# Drive.net
KiCad netlist of a schematic drawn in Altium Designer
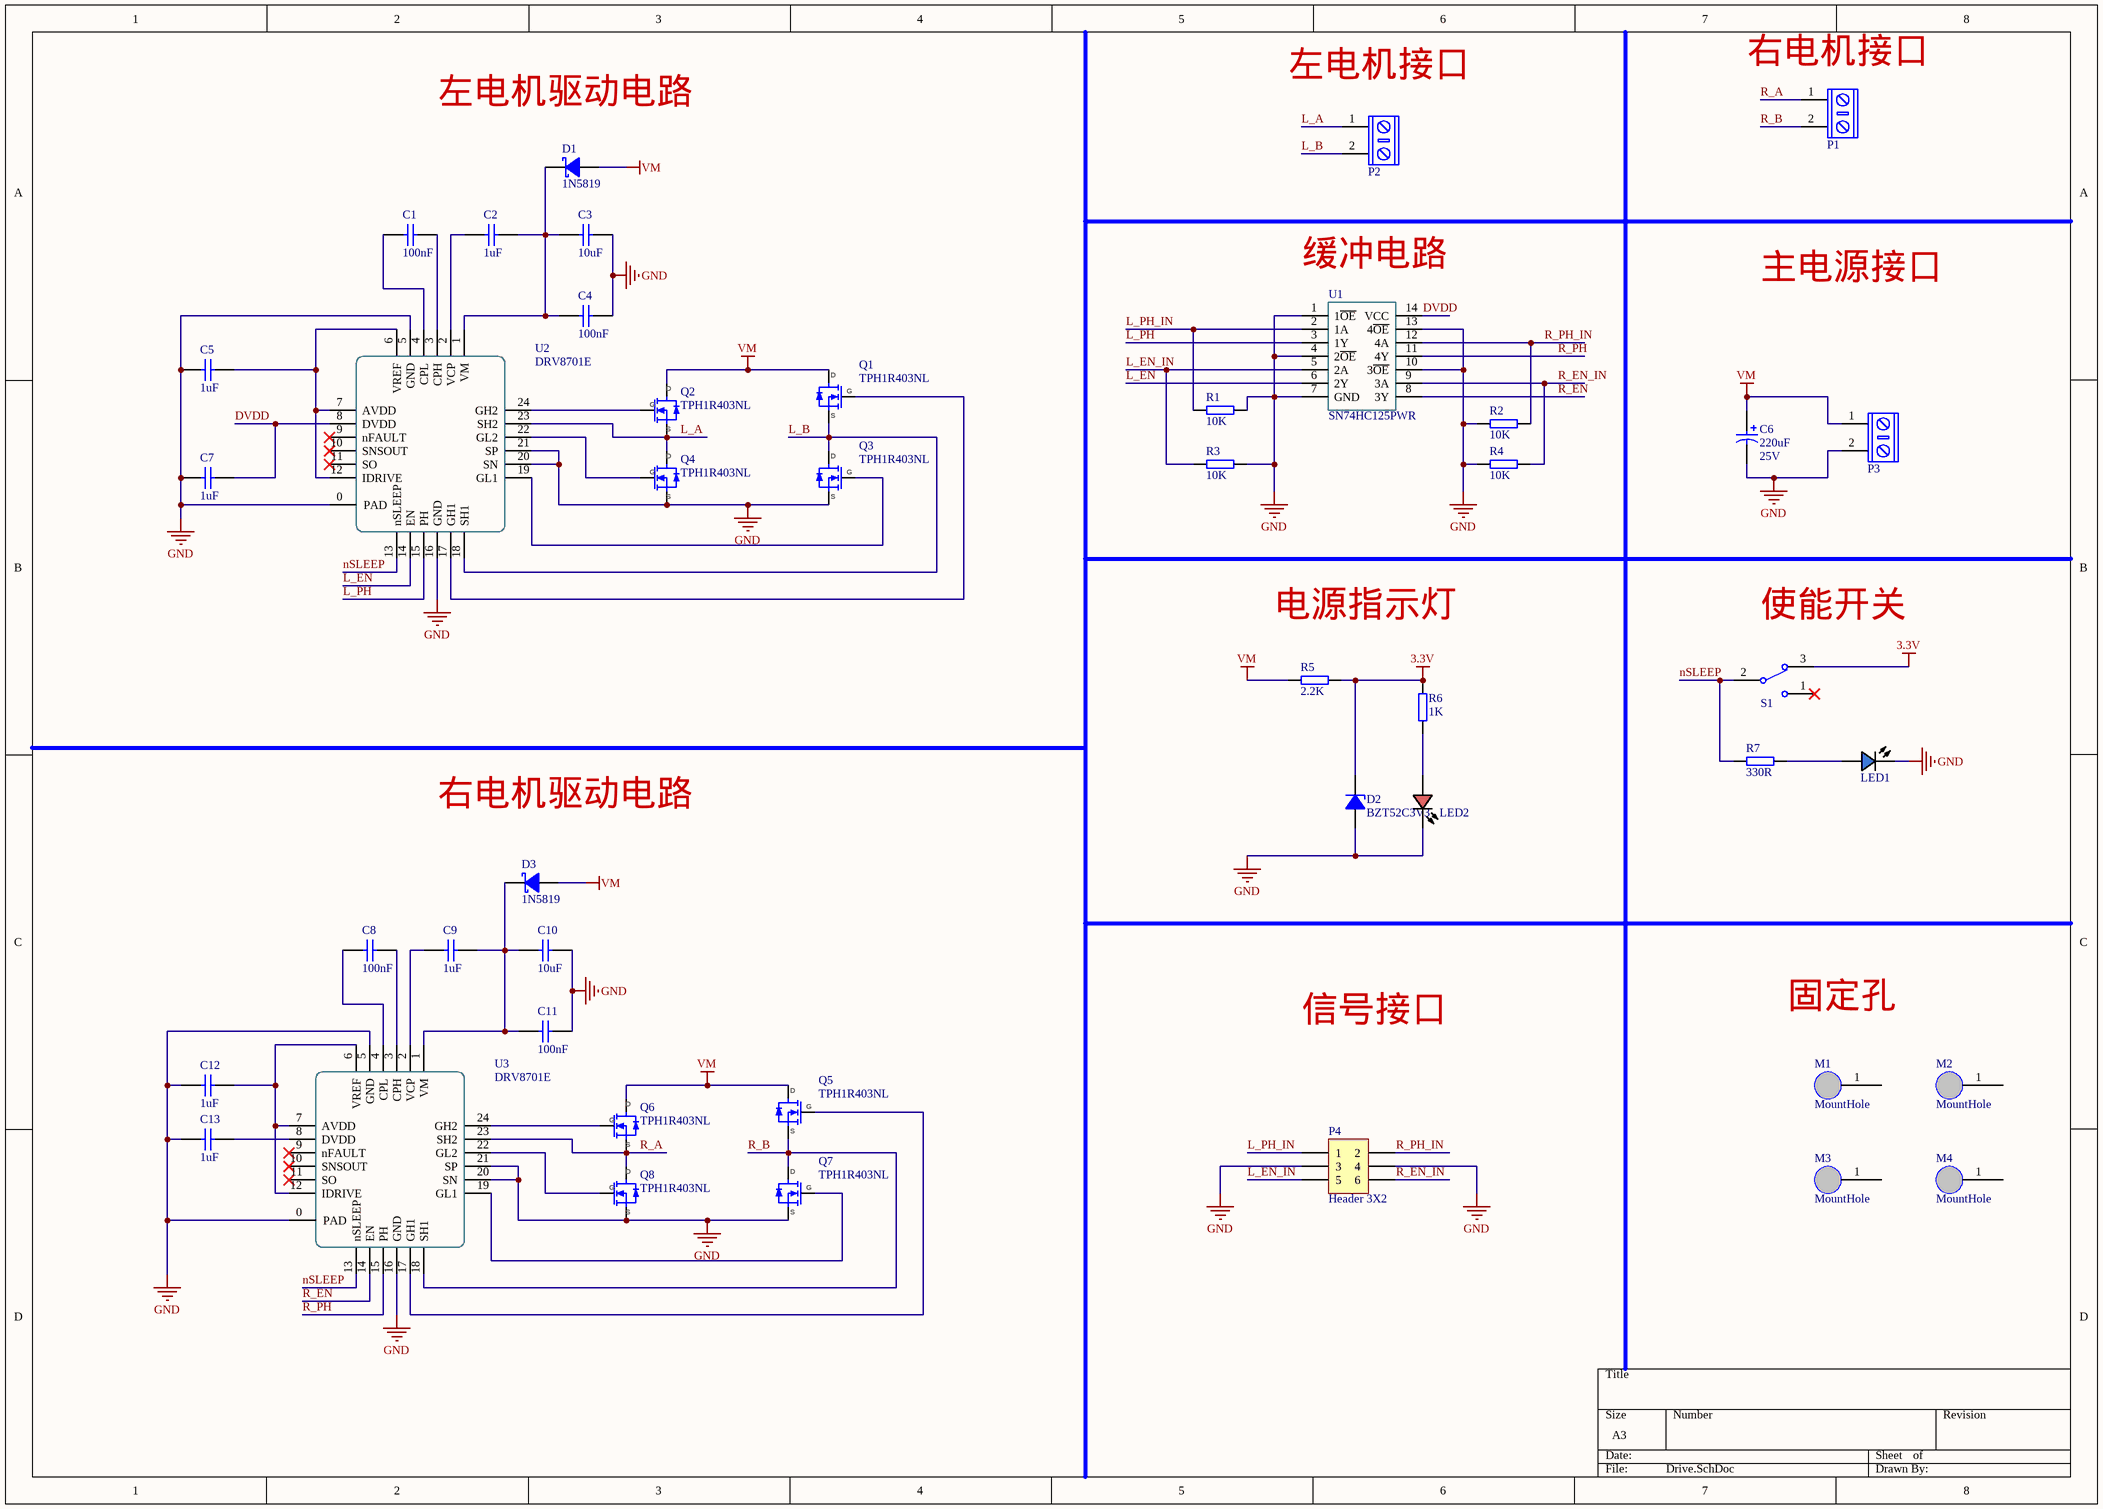
[diagram p0: Drive.SchDoc]

(export (version "E")
  (design (tool "Eeschema 10.0.6"))
  (components
    (comp (ref "C1")
      (value "100nF")
      (footprint "CAPC1608[0603]S-N")
      (description "贴片电容")
      (fields
        (field (name "VOLTAGE") "50V")
        (field (name "TOLERANCE") "±10%")
        (field (name "PUBLISHER") "Altium Limited")
      )
      (libsource (lib "DRV8701_DualMotorDriver") (part "Cap-Chip_1"))
    )
    (comp (ref "C2")
      (value "1uF")
      (footprint "CAPC1608[0603]S-N")
      (description "贴片电容")
      (fields
        (field (name "VOLTAGE") "25V")
        (field (name "TOLERANCE") "±10%")
        (field (name "PUBLISHER") "Altium Limited")
      )
      (libsource (lib "DRV8701_DualMotorDriver") (part "Cap-Chip_2"))
    )
    (comp (ref "C3")
      (value "10uF")
      (footprint "CAPC1608[0603]S-N")
      (description "贴片电容")
      (fields
        (field (name "VOLTAGE") "25V")
        (field (name "TOLERANCE") "±10%")
        (field (name "PUBLISHER") "Altium Limited")
      )
      (libsource (lib "DRV8701_DualMotorDriver") (part "Cap-Chip"))
    )
    (comp (ref "C4")
      (value "100nF")
      (footprint "CAPC1608[0603]S-N")
      (description "贴片电容")
      (fields
        (field (name "VOLTAGE") "50V")
        (field (name "TOLERANCE") "±10%")
        (field (name "PUBLISHER") "Altium Limited")
      )
      (libsource (lib "DRV8701_DualMotorDriver") (part "Cap-Chip_1"))
    )
    (comp (ref "C5")
      (value "1uF")
      (footprint "CAPC1608[0603]S-N")
      (description "贴片电容")
      (fields
        (field (name "VOLTAGE") "25V")
        (field (name "TOLERANCE") "±10%")
        (field (name "PUBLISHER") "Altium Limited")
      )
      (libsource (lib "DRV8701_DualMotorDriver") (part "Cap-Chip_2"))
    )
    (comp (ref "C6")
      (value "220uF")
      (footprint "CAPS6.3")
      (description "Polarized Capacitor (Radial)")
      (fields
        (field (name "VOLTAGE") "25V")
        (field (name "Comment") "220uF 25V")
        (field (name "PUBLISHER") "Altium Limited")
      )
      (libsource (lib "DRV8701_DualMotorDriver") (part "Cap-Elect"))
    )
    (comp (ref "C7")
      (value "1uF")
      (footprint "CAPC1608[0603]S-N")
      (description "贴片电容")
      (fields
        (field (name "VOLTAGE") "25V")
        (field (name "TOLERANCE") "±10%")
        (field (name "PUBLISHER") "Altium Limited")
      )
      (libsource (lib "DRV8701_DualMotorDriver") (part "Cap-Chip_2"))
    )
    (comp (ref "C8")
      (value "100nF")
      (footprint "CAPC1608[0603]S-N")
      (description "贴片电容")
      (fields
        (field (name "VOLTAGE") "50V")
        (field (name "TOLERANCE") "±10%")
        (field (name "PUBLISHER") "Altium Limited")
      )
      (libsource (lib "DRV8701_DualMotorDriver") (part "Cap-Chip_1"))
    )
    (comp (ref "C9")
      (value "1uF")
      (footprint "CAPC1608[0603]S-N")
      (description "贴片电容")
      (fields
        (field (name "VOLTAGE") "25V")
        (field (name "TOLERANCE") "±10%")
        (field (name "PUBLISHER") "Altium Limited")
      )
      (libsource (lib "DRV8701_DualMotorDriver") (part "Cap-Chip_2"))
    )
    (comp (ref "C10")
      (value "10uF")
      (footprint "CAPC1608[0603]S-N")
      (description "贴片电容")
      (fields
        (field (name "VOLTAGE") "25V")
        (field (name "TOLERANCE") "±10%")
        (field (name "PUBLISHER") "Altium Limited")
      )
      (libsource (lib "DRV8701_DualMotorDriver") (part "Cap-Chip"))
    )
    (comp (ref "C11")
      (value "100nF")
      (footprint "CAPC1608[0603]S-N")
      (description "贴片电容")
      (fields
        (field (name "VOLTAGE") "50V")
        (field (name "TOLERANCE") "±10%")
        (field (name "PUBLISHER") "Altium Limited")
      )
      (libsource (lib "DRV8701_DualMotorDriver") (part "Cap-Chip_1"))
    )
    (comp (ref "C12")
      (value "1uF")
      (footprint "CAPC1608[0603]S-N")
      (description "贴片电容")
      (fields
        (field (name "VOLTAGE") "25V")
        (field (name "TOLERANCE") "±10%")
        (field (name "PUBLISHER") "Altium Limited")
      )
      (libsource (lib "DRV8701_DualMotorDriver") (part "Cap-Chip_2"))
    )
    (comp (ref "C13")
      (value "1uF")
      (footprint "CAPC1608[0603]S-N")
      (description "贴片电容")
      (fields
        (field (name "VOLTAGE") "25V")
        (field (name "TOLERANCE") "±10%")
        (field (name "PUBLISHER") "Altium Limited")
      )
      (libsource (lib "DRV8701_DualMotorDriver") (part "Cap-Chip_2"))
    )
    (comp (ref "D1")
      (value "1N5819")
      (footprint "SOD-123-L")
      (description "肖特基二极管 Diode")
      (fields (field (name "PARTNUMBER") "1N5819") (field (name "PUBLISHER") "Altium Limited"))
      (libsource (lib "DRV8701_DualMotorDriver") (part "Diode Schottky"))
    )
    (comp (ref "D2")
      (value "BZT52C3V3")
      (footprint "SOD-123-L")
      (description "3.3V稳压二极管 SOD-123")
      (fields (field (name "PUBLISHER") "Altium Limited"))
      (libsource (lib "DRV8701_DualMotorDriver") (part "Diode Zen"))
    )
    (comp (ref "D3")
      (value "1N5819")
      (footprint "SOD-123-L")
      (description "肖特基二极管 Diode")
      (fields (field (name "PARTNUMBER") "1N5819") (field (name "PUBLISHER") "Altium Limited"))
      (libsource (lib "DRV8701_DualMotorDriver") (part "Diode Schottky"))
    )
    (comp (ref "LED1")
      (value "Blue")
      (footprint "LEDC1608(0603)")
      (description "Typical Chip LED")
      (fields (field (name "PUBLISHER") "Altium Limited"))
      (libsource (lib "DRV8701_DualMotorDriver") (part "LED Chip Blue"))
    )
    (comp (ref "LED2")
      (value "~")
      (footprint "LEDC1608(0603)")
      (description "Typical Chip LED")
      (fields (field (name "PUBLISHER") "Altium Limited"))
      (libsource (lib "DRV8701_DualMotorDriver") (part "LED Chip Red"))
    )
    (comp (ref "M1")
      (value "MountHole")
      (footprint "M3-MountSlot")
      (description "固定孔")
      (libsource (lib "DRV8701_DualMotorDriver") (part "MountHole"))
    )
    (comp (ref "M2")
      (value "MountHole")
      (footprint "M3-MountSlot")
      (description "固定孔")
      (libsource (lib "DRV8701_DualMotorDriver") (part "MountHole"))
    )
    (comp (ref "M3")
      (value "MountHole")
      (footprint "M3-MountSlot")
      (description "固定孔")
      (libsource (lib "DRV8701_DualMotorDriver") (part "MountHole"))
    )
    (comp (ref "M4")
      (value "MountHole")
      (footprint "M3-MountSlot")
      (description "固定孔")
      (libsource (lib "DRV8701_DualMotorDriver") (part "MountHole"))
    )
    (comp (ref "P1")
      (value "KF/WJ/DG 30x connecter")
      (footprint "KF/WJ/DG 301-2p-5.0mm")
      (description "接线端子 2Pin")
      (libsource (lib "DRV8701_DualMotorDriver") (part "KF/WJ/DG 30x"))
    )
    (comp (ref "P2")
      (value "KF/WJ/DG 30x connecter")
      (footprint "KF/WJ/DG 301-2p-5.0mm")
      (description "接线端子 2Pin")
      (libsource (lib "DRV8701_DualMotorDriver") (part "KF/WJ/DG 30x"))
    )
    (comp (ref "P3")
      (value "KF/WJ/DG 30x connecter")
      (footprint "KF/WJ/DG 301-2p-5.0mm")
      (description "接线端子 2Pin")
      (libsource (lib "DRV8701_DualMotorDriver") (part "KF/WJ/DG 30x"))
    )
    (comp (ref "P4")
      (value "Header 3X2")
      (footprint "HDR2X3")
      (description "Header, 3-Pin, Dual row")
      (fields (field (name "PUBLISHER") "Altium Limited"))
      (libsource (lib "DRV8701_DualMotorDriver") (part "Header 3X2"))
    )
    (comp (ref "Q1")
      (value "TPH1R403NL")
      (footprint "DFN5x6")
      (description "东芝 N沟 MOS")
      (libsource (lib "DRV8701_DualMotorDriver") (part "TPH1R403NL"))
    )
    (comp (ref "Q2")
      (value "TPH1R403NL")
      (footprint "DFN5x6")
      (description "东芝 N沟 MOS")
      (libsource (lib "DRV8701_DualMotorDriver") (part "TPH1R403NL"))
    )
    (comp (ref "Q3")
      (value "TPH1R403NL")
      (footprint "DFN5x6")
      (description "东芝 N沟 MOS")
      (libsource (lib "DRV8701_DualMotorDriver") (part "TPH1R403NL"))
    )
    (comp (ref "Q4")
      (value "TPH1R403NL")
      (footprint "DFN5x6")
      (description "东芝 N沟 MOS")
      (libsource (lib "DRV8701_DualMotorDriver") (part "TPH1R403NL"))
    )
    (comp (ref "Q5")
      (value "TPH1R403NL")
      (footprint "DFN5x6")
      (description "东芝 N沟 MOS")
      (libsource (lib "DRV8701_DualMotorDriver") (part "TPH1R403NL"))
    )
    (comp (ref "Q6")
      (value "TPH1R403NL")
      (footprint "DFN5x6")
      (description "东芝 N沟 MOS")
      (libsource (lib "DRV8701_DualMotorDriver") (part "TPH1R403NL"))
    )
    (comp (ref "Q7")
      (value "TPH1R403NL")
      (footprint "DFN5x6")
      (description "东芝 N沟 MOS")
      (libsource (lib "DRV8701_DualMotorDriver") (part "TPH1R403NL"))
    )
    (comp (ref "Q8")
      (value "TPH1R403NL")
      (footprint "DFN5x6")
      (description "东芝 N沟 MOS")
      (libsource (lib "DRV8701_DualMotorDriver") (part "TPH1R403NL"))
    )
    (comp (ref "R1")
      (value "10K")
      (footprint "RESC1608[0603]S-N")
      (description "贴片电阻")
      (fields
        (field (name "TOLERANCE") "±1%")
        (field (name "Comment") "10K ±1%")
        (field (name "PUBLISHER") "Altium Limited")
      )
      (libsource (lib "DRV8701_DualMotorDriver") (part "Res-Chip_1"))
    )
    (comp (ref "R2")
      (value "10K")
      (footprint "RESC1608[0603]S-N")
      (description "贴片电阻")
      (fields
        (field (name "TOLERANCE") "±1%")
        (field (name "Comment") "10K ±1%")
        (field (name "PUBLISHER") "Altium Limited")
      )
      (libsource (lib "DRV8701_DualMotorDriver") (part "Res-Chip_1"))
    )
    (comp (ref "R3")
      (value "10K")
      (footprint "RESC1608[0603]S-N")
      (description "贴片电阻")
      (fields
        (field (name "TOLERANCE") "±1%")
        (field (name "Comment") "10K ±1%")
        (field (name "PUBLISHER") "Altium Limited")
      )
      (libsource (lib "DRV8701_DualMotorDriver") (part "Res-Chip_1"))
    )
    (comp (ref "R4")
      (value "10K")
      (footprint "RESC1608[0603]S-N")
      (description "贴片电阻")
      (fields
        (field (name "TOLERANCE") "±1%")
        (field (name "Comment") "10K ±1%")
        (field (name "PUBLISHER") "Altium Limited")
      )
      (libsource (lib "DRV8701_DualMotorDriver") (part "Res-Chip_1"))
    )
    (comp (ref "R5")
      (value "2.2K")
      (footprint "RESC1608[0603]S-N")
      (description "贴片电阻")
      (fields
        (field (name "TOLERANCE") "±1%")
        (field (name "Comment") "2.2K ±1%")
        (field (name "PUBLISHER") "Altium Limited")
      )
      (libsource (lib "DRV8701_DualMotorDriver") (part "Res-Chip"))
    )
    (comp (ref "R6")
      (value "1K")
      (footprint "RESC1608[0603]S-N")
      (description "贴片电阻")
      (fields
        (field (name "TOLERANCE") "±1%")
        (field (name "Comment") "1K ±1%")
        (field (name "PUBLISHER") "Altium Limited")
      )
      (libsource (lib "DRV8701_DualMotorDriver") (part "Res-Chip_2"))
    )
    (comp (ref "R7")
      (value "330R")
      (footprint "RESC1608[0603]S-N")
      (description "贴片电阻")
      (fields
        (field (name "TOLERANCE") "±1%")
        (field (name "Comment") "330R ±1%")
        (field (name "PUBLISHER") "Altium Limited")
      )
      (libsource (lib "DRV8701_DualMotorDriver") (part "Res-Chip_3"))
    )
    (comp (ref "S1")
      (value "SW-SPDT")
      (footprint "SS12D10")
      (description "单刀双掷开关 3脚船型、钮子、拨动开关 SPDT Subminiature Toggle Switch")
      (fields (field (name "PUBLISHER") "Altium Limited"))
      (libsource (lib "DRV8701_DualMotorDriver") (part "SW-SPDT"))
    )
    (comp (ref "U1")
      (value "SN74HC125PWR")
      (footprint "TSSOP-14")
      (description "三态输出的四路缓冲器 TSSOP-20")
      (libsource (lib "DRV8701_DualMotorDriver") (part "SN74HC125PWR"))
    )
    (comp (ref "U2")
      (value "DRV8701E")
      (footprint "QFN24-4x4")
      (description "DRV8701E Ti全桥驱动芯片")
      (libsource (lib "DRV8701_DualMotorDriver") (part "DRV8701E"))
    )
    (comp (ref "U3")
      (value "DRV8701E")
      (footprint "QFN24-4x4")
      (description "DRV8701E Ti全桥驱动芯片")
      (libsource (lib "DRV8701_DualMotorDriver") (part "DRV8701E"))
    )
  )
  (nets
    (net (code "1") (name "/DVDD") (class "Default")
      (node (ref "C7") (pin "2") (pinfunction "2_2") (pintype "passive"))
      (node (ref "U1") (pin "14") (pinfunction "VCC_14") (pintype "passive"))
      (node (ref "U2") (pin "8") (pinfunction "DVDD_8") (pintype "passive"))
    )
    (net (code "2") (name "/L_A") (class "Default")
      (node (ref "P2") (pin "1") (pinfunction "1_1") (pintype "passive"))
      (node (ref "Q2") (pin "3") (pinfunction "S_3") (pintype "passive"))
      (node (ref "Q4") (pin "1") (pinfunction "D_1") (pintype "passive"))
      (node (ref "U2") (pin "23") (pinfunction "SH2_23") (pintype "passive"))
    )
    (net (code "3") (name "/L_B") (class "Default")
      (node (ref "P2") (pin "2") (pinfunction "2_2") (pintype "passive"))
      (node (ref "Q1") (pin "3") (pinfunction "S_3") (pintype "passive"))
      (node (ref "Q3") (pin "1") (pinfunction "D_1") (pintype "passive"))
      (node (ref "U2") (pin "18") (pinfunction "SH1_18") (pintype "passive"))
    )
    (net (code "4") (name "/L_EN") (class "Default")
      (node (ref "U1") (pin "6") (pinfunction "2Y_6") (pintype "passive"))
      (node (ref "U2") (pin "14") (pinfunction "EN_14") (pintype "passive"))
    )
    (net (code "5") (name "/L_EN_IN") (class "Default")
      (node (ref "P4") (pin "5") (pinfunction "5_5") (pintype "passive"))
      (node (ref "R3") (pin "1") (pinfunction "1_1") (pintype "passive"))
      (node (ref "U1") (pin "5") (pinfunction "2A_5") (pintype "passive"))
    )
    (net (code "6") (name "/L_PH") (class "Default")
      (node (ref "U1") (pin "3") (pinfunction "1Y_3") (pintype "passive"))
      (node (ref "U2") (pin "15") (pinfunction "PH_15") (pintype "passive"))
    )
    (net (code "7") (name "/L_PH_IN") (class "Default")
      (node (ref "P4") (pin "1") (pinfunction "1_1") (pintype "passive"))
      (node (ref "R1") (pin "1") (pinfunction "1_1") (pintype "passive"))
      (node (ref "U1") (pin "2") (pinfunction "1A_2") (pintype "passive"))
    )
    (net (code "8") (name "/R_A") (class "Default")
      (node (ref "P1") (pin "1") (pinfunction "1_1") (pintype "passive"))
      (node (ref "Q6") (pin "3") (pinfunction "S_3") (pintype "passive"))
      (node (ref "Q8") (pin "1") (pinfunction "D_1") (pintype "passive"))
      (node (ref "U3") (pin "23") (pinfunction "SH2_23") (pintype "passive"))
    )
    (net (code "9") (name "/R_B") (class "Default")
      (node (ref "P1") (pin "2") (pinfunction "2_2") (pintype "passive"))
      (node (ref "Q5") (pin "3") (pinfunction "S_3") (pintype "passive"))
      (node (ref "Q7") (pin "1") (pinfunction "D_1") (pintype "passive"))
      (node (ref "U3") (pin "18") (pinfunction "SH1_18") (pintype "passive"))
    )
    (net (code "10") (name "/R_EN") (class "Default")
      (node (ref "U1") (pin "8") (pinfunction "3Y_8") (pintype "passive"))
      (node (ref "U3") (pin "14") (pinfunction "EN_14") (pintype "passive"))
    )
    (net (code "11") (name "/R_EN_IN") (class "Default")
      (node (ref "P4") (pin "6") (pinfunction "6_6") (pintype "passive"))
      (node (ref "R4") (pin "2") (pinfunction "2_2") (pintype "passive"))
      (node (ref "U1") (pin "9") (pinfunction "3A_9") (pintype "passive"))
    )
    (net (code "12") (name "/R_PH") (class "Default")
      (node (ref "U1") (pin "11") (pinfunction "4Y_11") (pintype "passive"))
      (node (ref "U3") (pin "15") (pinfunction "PH_15") (pintype "passive"))
    )
    (net (code "13") (name "/R_PH_IN") (class "Default")
      (node (ref "P4") (pin "2") (pinfunction "2_2") (pintype "passive"))
      (node (ref "R2") (pin "2") (pinfunction "2_2") (pintype "passive"))
      (node (ref "U1") (pin "12") (pinfunction "4A_12") (pintype "passive"))
    )
    (net (code "14") (name "/nSLEEP") (class "Default")
      (node (ref "R7") (pin "1") (pinfunction "1_1") (pintype "passive"))
      (node (ref "S1") (pin "2") (pintype "passive"))
      (node (ref "U2") (pin "13") (pinfunction "nSLEEP_13") (pintype "passive"))
      (node (ref "U3") (pin "13") (pinfunction "nSLEEP_13") (pintype "passive"))
    )
    (net (code "15") (name "3.3V") (class "Default")
      (node (ref "D2") (pin "K") (pinfunction "K_K") (pintype "passive"))
      (node (ref "R5") (pin "2") (pinfunction "2_2") (pintype "passive"))
      (node (ref "R6") (pin "2") (pinfunction "2_2") (pintype "passive"))
      (node (ref "S1") (pin "3") (pintype "passive"))
    )
    (net (code "16") (name "GND") (class "Default")
      (node (ref "C10") (pin "2") (pinfunction "2_2") (pintype "passive"))
      (node (ref "C11") (pin "2") (pinfunction "2_2") (pintype "passive"))
      (node (ref "C12") (pin "1") (pinfunction "1_1") (pintype "passive"))
      (node (ref "C13") (pin "1") (pinfunction "1_1") (pintype "passive"))
      (node (ref "C3") (pin "2") (pinfunction "2_2") (pintype "passive"))
      (node (ref "C4") (pin "2") (pinfunction "2_2") (pintype "passive"))
      (node (ref "C5") (pin "1") (pinfunction "1_1") (pintype "passive"))
      (node (ref "C6") (pin "2") (pinfunction "2_2") (pintype "passive"))
      (node (ref "C7") (pin "1") (pinfunction "1_1") (pintype "passive"))
      (node (ref "D2") (pin "A") (pinfunction "A_A") (pintype "passive"))
      (node (ref "LED1") (pin "C") (pinfunction "C_C") (pintype "passive"))
      (node (ref "LED2") (pin "C") (pinfunction "C_C") (pintype "passive"))
      (node (ref "P3") (pin "2") (pinfunction "2_2") (pintype "passive"))
      (node (ref "P4") (pin "3") (pinfunction "3_3") (pintype "passive"))
      (node (ref "P4") (pin "4") (pinfunction "4_4") (pintype "passive"))
      (node (ref "Q3") (pin "3") (pinfunction "S_3") (pintype "passive"))
      (node (ref "Q4") (pin "3") (pinfunction "S_3") (pintype "passive"))
      (node (ref "Q7") (pin "3") (pinfunction "S_3") (pintype "passive"))
      (node (ref "Q8") (pin "3") (pinfunction "S_3") (pintype "passive"))
      (node (ref "R1") (pin "2") (pinfunction "2_2") (pintype "passive"))
      (node (ref "R2") (pin "1") (pinfunction "1_1") (pintype "passive"))
      (node (ref "R3") (pin "2") (pinfunction "2_2") (pintype "passive"))
      (node (ref "R4") (pin "1") (pinfunction "1_1") (pintype "passive"))
      (node (ref "U1") (pin "1") (pinfunction "1~{OE}_1") (pintype "passive"))
      (node (ref "U1") (pin "10") (pinfunction "3~{OE}_10") (pintype "passive"))
      (node (ref "U1") (pin "13") (pinfunction "4~{OE}_13") (pintype "passive"))
      (node (ref "U1") (pin "4") (pinfunction "2~{OE}_4") (pintype "passive"))
      (node (ref "U1") (pin "7") (pinfunction "GND_7") (pintype "passive"))
      (node (ref "U2") (pin "0") (pinfunction "PAD_0") (pintype "passive"))
      (node (ref "U2") (pin "16") (pinfunction "GND_16") (pintype "passive"))
      (node (ref "U2") (pin "20") (pinfunction "SN_20") (pintype "passive"))
      (node (ref "U2") (pin "21") (pinfunction "SP_21") (pintype "passive"))
      (node (ref "U2") (pin "5") (pinfunction "GND_5") (pintype "passive"))
      (node (ref "U3") (pin "0") (pinfunction "PAD_0") (pintype "passive"))
      (node (ref "U3") (pin "16") (pinfunction "GND_16") (pintype "passive"))
      (node (ref "U3") (pin "20") (pinfunction "SN_20") (pintype "passive"))
      (node (ref "U3") (pin "21") (pinfunction "SP_21") (pintype "passive"))
      (node (ref "U3") (pin "5") (pinfunction "GND_5") (pintype "passive"))
    )
    (net (code "17") (name "Net-(LED1-PadA)") (class "Default")
      (node (ref "LED1") (pin "A") (pinfunction "A_A") (pintype "passive"))
      (node (ref "R7") (pin "2") (pinfunction "2_2") (pintype "passive"))
    )
    (net (code "18") (name "Net-(LED2-PadA)") (class "Default")
      (node (ref "LED2") (pin "A") (pinfunction "A_A") (pintype "passive"))
      (node (ref "R6") (pin "1") (pinfunction "1_1") (pintype "passive"))
    )
    (net (code "19") (name "Net-(Q1-G)") (class "Default")
      (node (ref "Q1") (pin "2") (pinfunction "G_2") (pintype "passive"))
      (node (ref "U2") (pin "17") (pinfunction "GH1_17") (pintype "passive"))
    )
    (net (code "20") (name "Net-(Q2-G)") (class "Default")
      (node (ref "Q2") (pin "2") (pinfunction "G_2") (pintype "passive"))
      (node (ref "U2") (pin "24") (pinfunction "GH2_24") (pintype "passive"))
    )
    (net (code "21") (name "Net-(Q3-G)") (class "Default")
      (node (ref "Q3") (pin "2") (pinfunction "G_2") (pintype "passive"))
      (node (ref "U2") (pin "19") (pinfunction "GL1_19") (pintype "passive"))
    )
    (net (code "22") (name "Net-(Q4-G)") (class "Default")
      (node (ref "Q4") (pin "2") (pinfunction "G_2") (pintype "passive"))
      (node (ref "U2") (pin "22") (pinfunction "GL2_22") (pintype "passive"))
    )
    (net (code "23") (name "Net-(Q5-G)") (class "Default")
      (node (ref "Q5") (pin "2") (pinfunction "G_2") (pintype "passive"))
      (node (ref "U3") (pin "17") (pinfunction "GH1_17") (pintype "passive"))
    )
    (net (code "24") (name "Net-(Q6-G)") (class "Default")
      (node (ref "Q6") (pin "2") (pinfunction "G_2") (pintype "passive"))
      (node (ref "U3") (pin "24") (pinfunction "GH2_24") (pintype "passive"))
    )
    (net (code "25") (name "Net-(Q7-G)") (class "Default")
      (node (ref "Q7") (pin "2") (pinfunction "G_2") (pintype "passive"))
      (node (ref "U3") (pin "19") (pinfunction "GL1_19") (pintype "passive"))
    )
    (net (code "26") (name "Net-(Q8-G)") (class "Default")
      (node (ref "Q8") (pin "2") (pinfunction "G_2") (pintype "passive"))
      (node (ref "U3") (pin "22") (pinfunction "GL2_22") (pintype "passive"))
    )
    (net (code "27") (name "Net-(U2-AVDD)") (class "Default")
      (node (ref "C5") (pin "2") (pinfunction "2_2") (pintype "passive"))
      (node (ref "U2") (pin "12") (pinfunction "IDRIVE_12") (pintype "passive"))
      (node (ref "U2") (pin "6") (pinfunction "VREF_6") (pintype "passive"))
      (node (ref "U2") (pin "7") (pinfunction "AVDD_7") (pintype "passive"))
    )
    (net (code "28") (name "Net-(U2-CPH)") (class "Default")
      (node (ref "C1") (pin "2") (pinfunction "2_2") (pintype "passive"))
      (node (ref "U2") (pin "3") (pinfunction "CPH_3") (pintype "passive"))
    )
    (net (code "29") (name "Net-(U2-CPL)") (class "Default")
      (node (ref "C1") (pin "1") (pinfunction "1_1") (pintype "passive"))
      (node (ref "U2") (pin "4") (pinfunction "CPL_4") (pintype "passive"))
    )
    (net (code "30") (name "Net-(U2-VCP)") (class "Default")
      (node (ref "C2") (pin "1") (pinfunction "1_1") (pintype "passive"))
      (node (ref "U2") (pin "2") (pinfunction "VCP_2") (pintype "passive"))
    )
    (net (code "31") (name "Net-(U2-VM)") (class "Default")
      (node (ref "C2") (pin "2") (pinfunction "2_2") (pintype "passive"))
      (node (ref "C3") (pin "1") (pinfunction "1_1") (pintype "passive"))
      (node (ref "C4") (pin "1") (pinfunction "1_1") (pintype "passive"))
      (node (ref "D1") (pin "K") (pinfunction "K_K") (pintype "passive"))
      (node (ref "U2") (pin "1") (pinfunction "VM_1") (pintype "passive"))
    )
    (net (code "32") (name "Net-(U3-AVDD)") (class "Default")
      (node (ref "C12") (pin "2") (pinfunction "2_2") (pintype "passive"))
      (node (ref "U3") (pin "12") (pinfunction "IDRIVE_12") (pintype "passive"))
      (node (ref "U3") (pin "6") (pinfunction "VREF_6") (pintype "passive"))
      (node (ref "U3") (pin "7") (pinfunction "AVDD_7") (pintype "passive"))
    )
    (net (code "33") (name "Net-(U3-CPH)") (class "Default")
      (node (ref "C8") (pin "2") (pinfunction "2_2") (pintype "passive"))
      (node (ref "U3") (pin "3") (pinfunction "CPH_3") (pintype "passive"))
    )
    (net (code "34") (name "Net-(U3-CPL)") (class "Default")
      (node (ref "C8") (pin "1") (pinfunction "1_1") (pintype "passive"))
      (node (ref "U3") (pin "4") (pinfunction "CPL_4") (pintype "passive"))
    )
    (net (code "35") (name "Net-(U3-DVDD)") (class "Default")
      (node (ref "C13") (pin "2") (pinfunction "2_2") (pintype "passive"))
      (node (ref "U3") (pin "8") (pinfunction "DVDD_8") (pintype "passive"))
    )
    (net (code "36") (name "Net-(U3-VCP)") (class "Default")
      (node (ref "C9") (pin "1") (pinfunction "1_1") (pintype "passive"))
      (node (ref "U3") (pin "2") (pinfunction "VCP_2") (pintype "passive"))
    )
    (net (code "37") (name "Net-(U3-VM)") (class "Default")
      (node (ref "C10") (pin "1") (pinfunction "1_1") (pintype "passive"))
      (node (ref "C11") (pin "1") (pinfunction "1_1") (pintype "passive"))
      (node (ref "C9") (pin "2") (pinfunction "2_2") (pintype "passive"))
      (node (ref "D3") (pin "K") (pinfunction "K_K") (pintype "passive"))
      (node (ref "U3") (pin "1") (pinfunction "VM_1") (pintype "passive"))
    )
    (net (code "38") (name "VM") (class "Default")
      (node (ref "C6") (pin "1") (pinfunction "1_1") (pintype "passive"))
      (node (ref "D1") (pin "A") (pinfunction "A_A") (pintype "passive"))
      (node (ref "D3") (pin "A") (pinfunction "A_A") (pintype "passive"))
      (node (ref "P3") (pin "1") (pinfunction "1_1") (pintype "passive"))
      (node (ref "Q1") (pin "1") (pinfunction "D_1") (pintype "passive"))
      (node (ref "Q2") (pin "1") (pinfunction "D_1") (pintype "passive"))
      (node (ref "Q5") (pin "1") (pinfunction "D_1") (pintype "passive"))
      (node (ref "Q6") (pin "1") (pinfunction "D_1") (pintype "passive"))
      (node (ref "R5") (pin "1") (pinfunction "1_1") (pintype "passive"))
    )
    (net (code "39") (name "unconnected-(M1-Pad1)") (class "Default")
      (node (ref "M1") (pin "1") (pinfunction "1_1") (pintype "passive"))
    )
    (net (code "40") (name "unconnected-(M2-Pad1)") (class "Default")
      (node (ref "M2") (pin "1") (pinfunction "1_1") (pintype "passive"))
    )
    (net (code "41") (name "unconnected-(M3-Pad1)") (class "Default")
      (node (ref "M3") (pin "1") (pinfunction "1_1") (pintype "passive"))
    )
    (net (code "42") (name "unconnected-(M4-Pad1)") (class "Default")
      (node (ref "M4") (pin "1") (pinfunction "1_1") (pintype "passive"))
    )
    (net (code "43") (name "unconnected-(S1-Pad1)") (class "Default")
      (node (ref "S1") (pin "1") (pintype "passive+no_connect"))
    )
    (net (code "44") (name "unconnected-(U2-SNSOUT-Pad10)") (class "Default")
      (node (ref "U2") (pin "10") (pinfunction "SNSOUT_10") (pintype "passive+no_connect"))
    )
    (net (code "45") (name "unconnected-(U2-SO-Pad11)") (class "Default")
      (node (ref "U2") (pin "11") (pinfunction "SO_11") (pintype "passive+no_connect"))
    )
    (net (code "46") (name "unconnected-(U2-nFAULT-Pad9)") (class "Default")
      (node (ref "U2") (pin "9") (pinfunction "nFAULT_9") (pintype "passive+no_connect"))
    )
    (net (code "47") (name "unconnected-(U3-SNSOUT-Pad10)") (class "Default")
      (node (ref "U3") (pin "10") (pinfunction "SNSOUT_10") (pintype "passive+no_connect"))
    )
    (net (code "48") (name "unconnected-(U3-SO-Pad11)") (class "Default")
      (node (ref "U3") (pin "11") (pinfunction "SO_11") (pintype "passive+no_connect"))
    )
    (net (code "49") (name "unconnected-(U3-nFAULT-Pad9)") (class "Default")
      (node (ref "U3") (pin "9") (pinfunction "nFAULT_9") (pintype "passive+no_connect"))
    )
  )
)
